# wchair.net
KiCad netlist of a schematic drawn in EAGLE
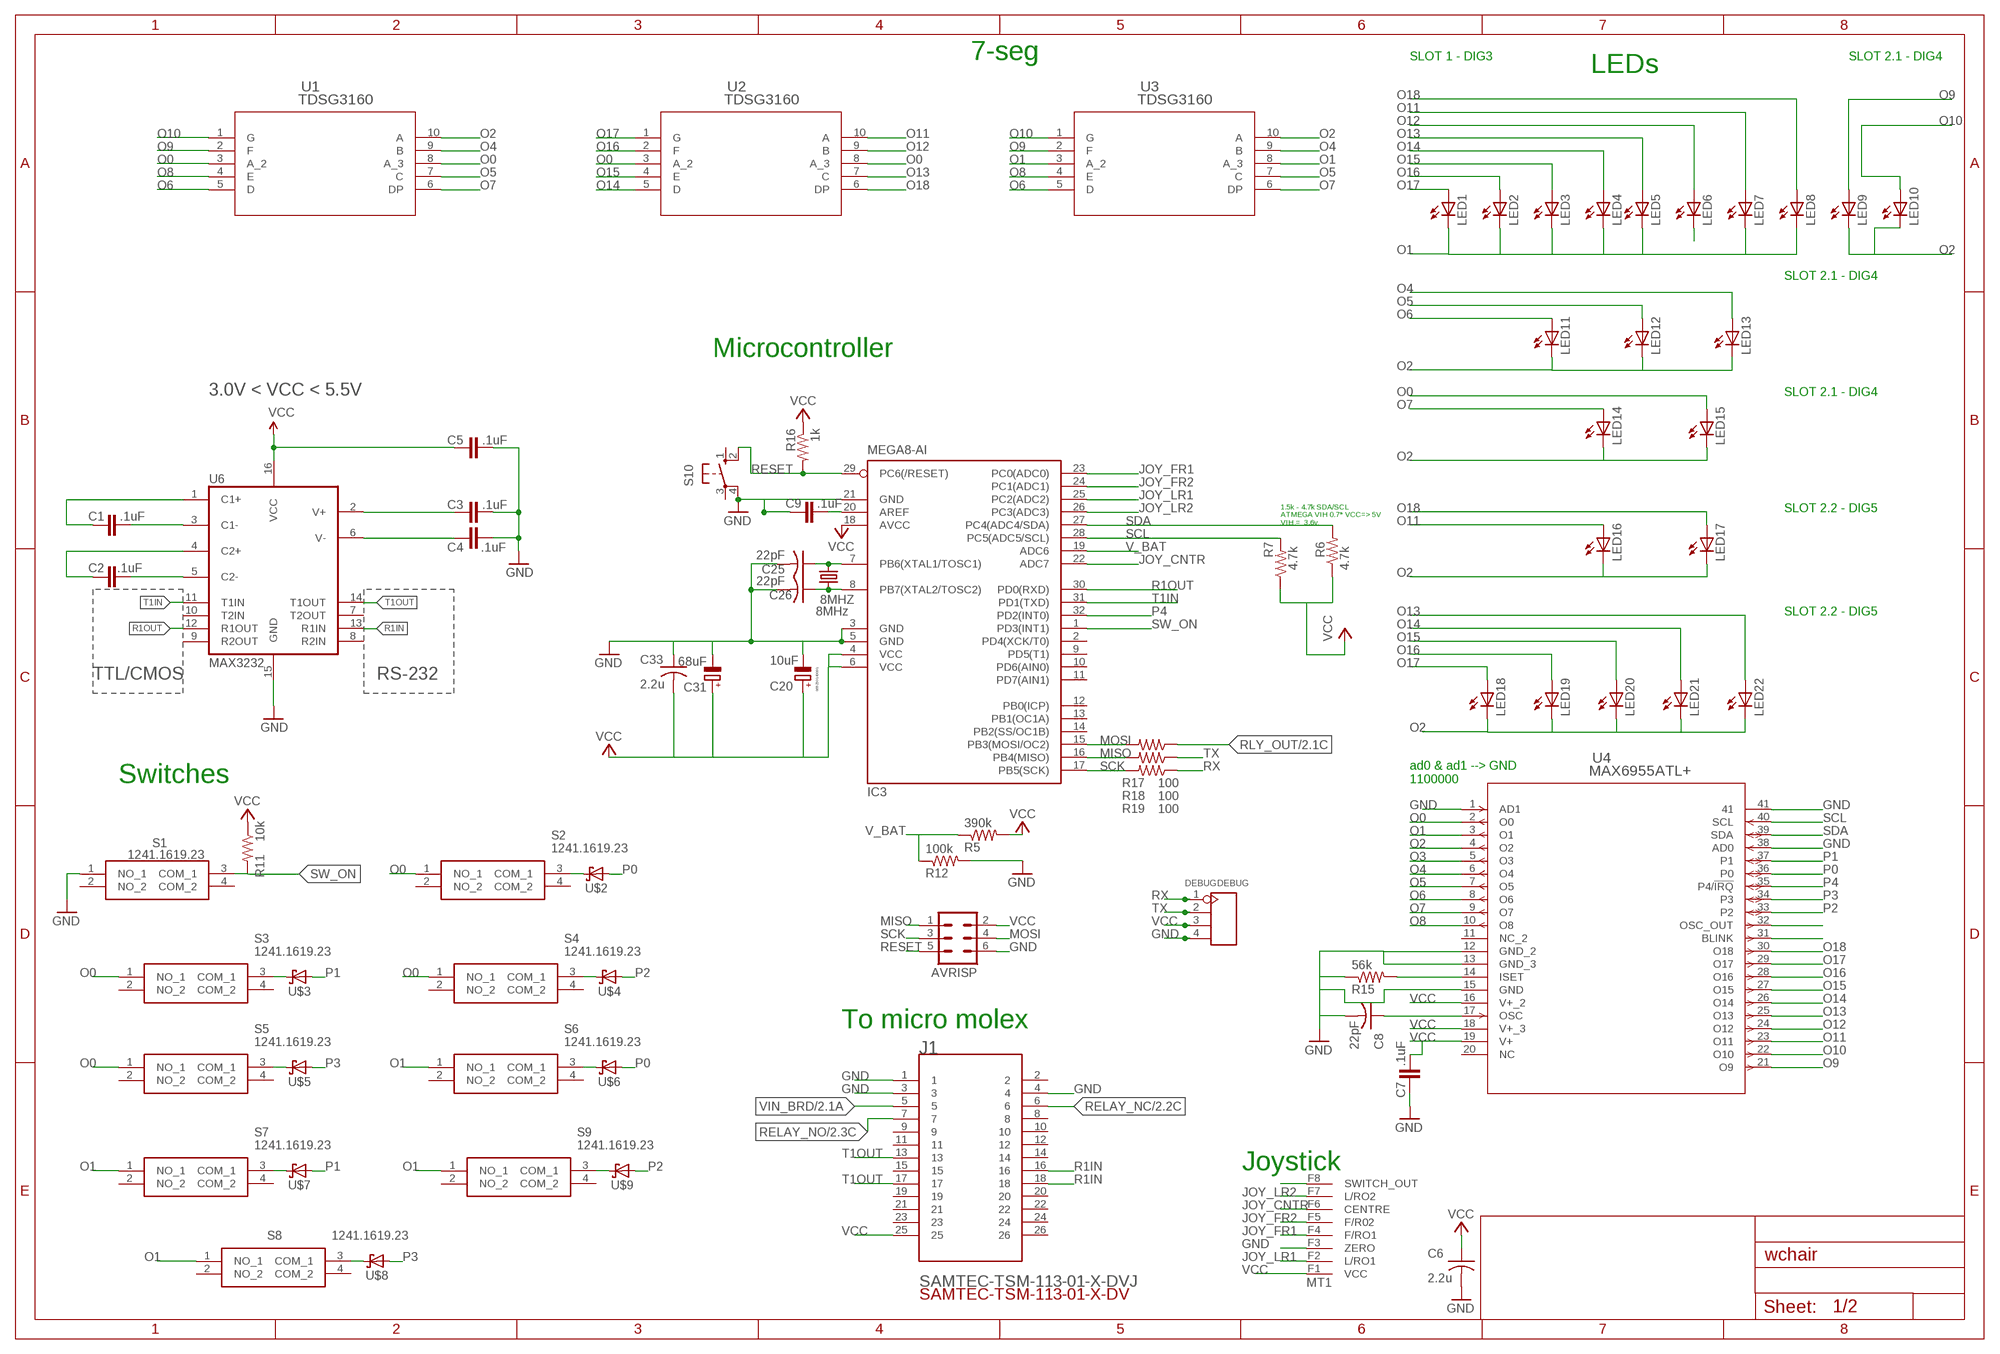
[diagram p0: schematic, sheet 1]
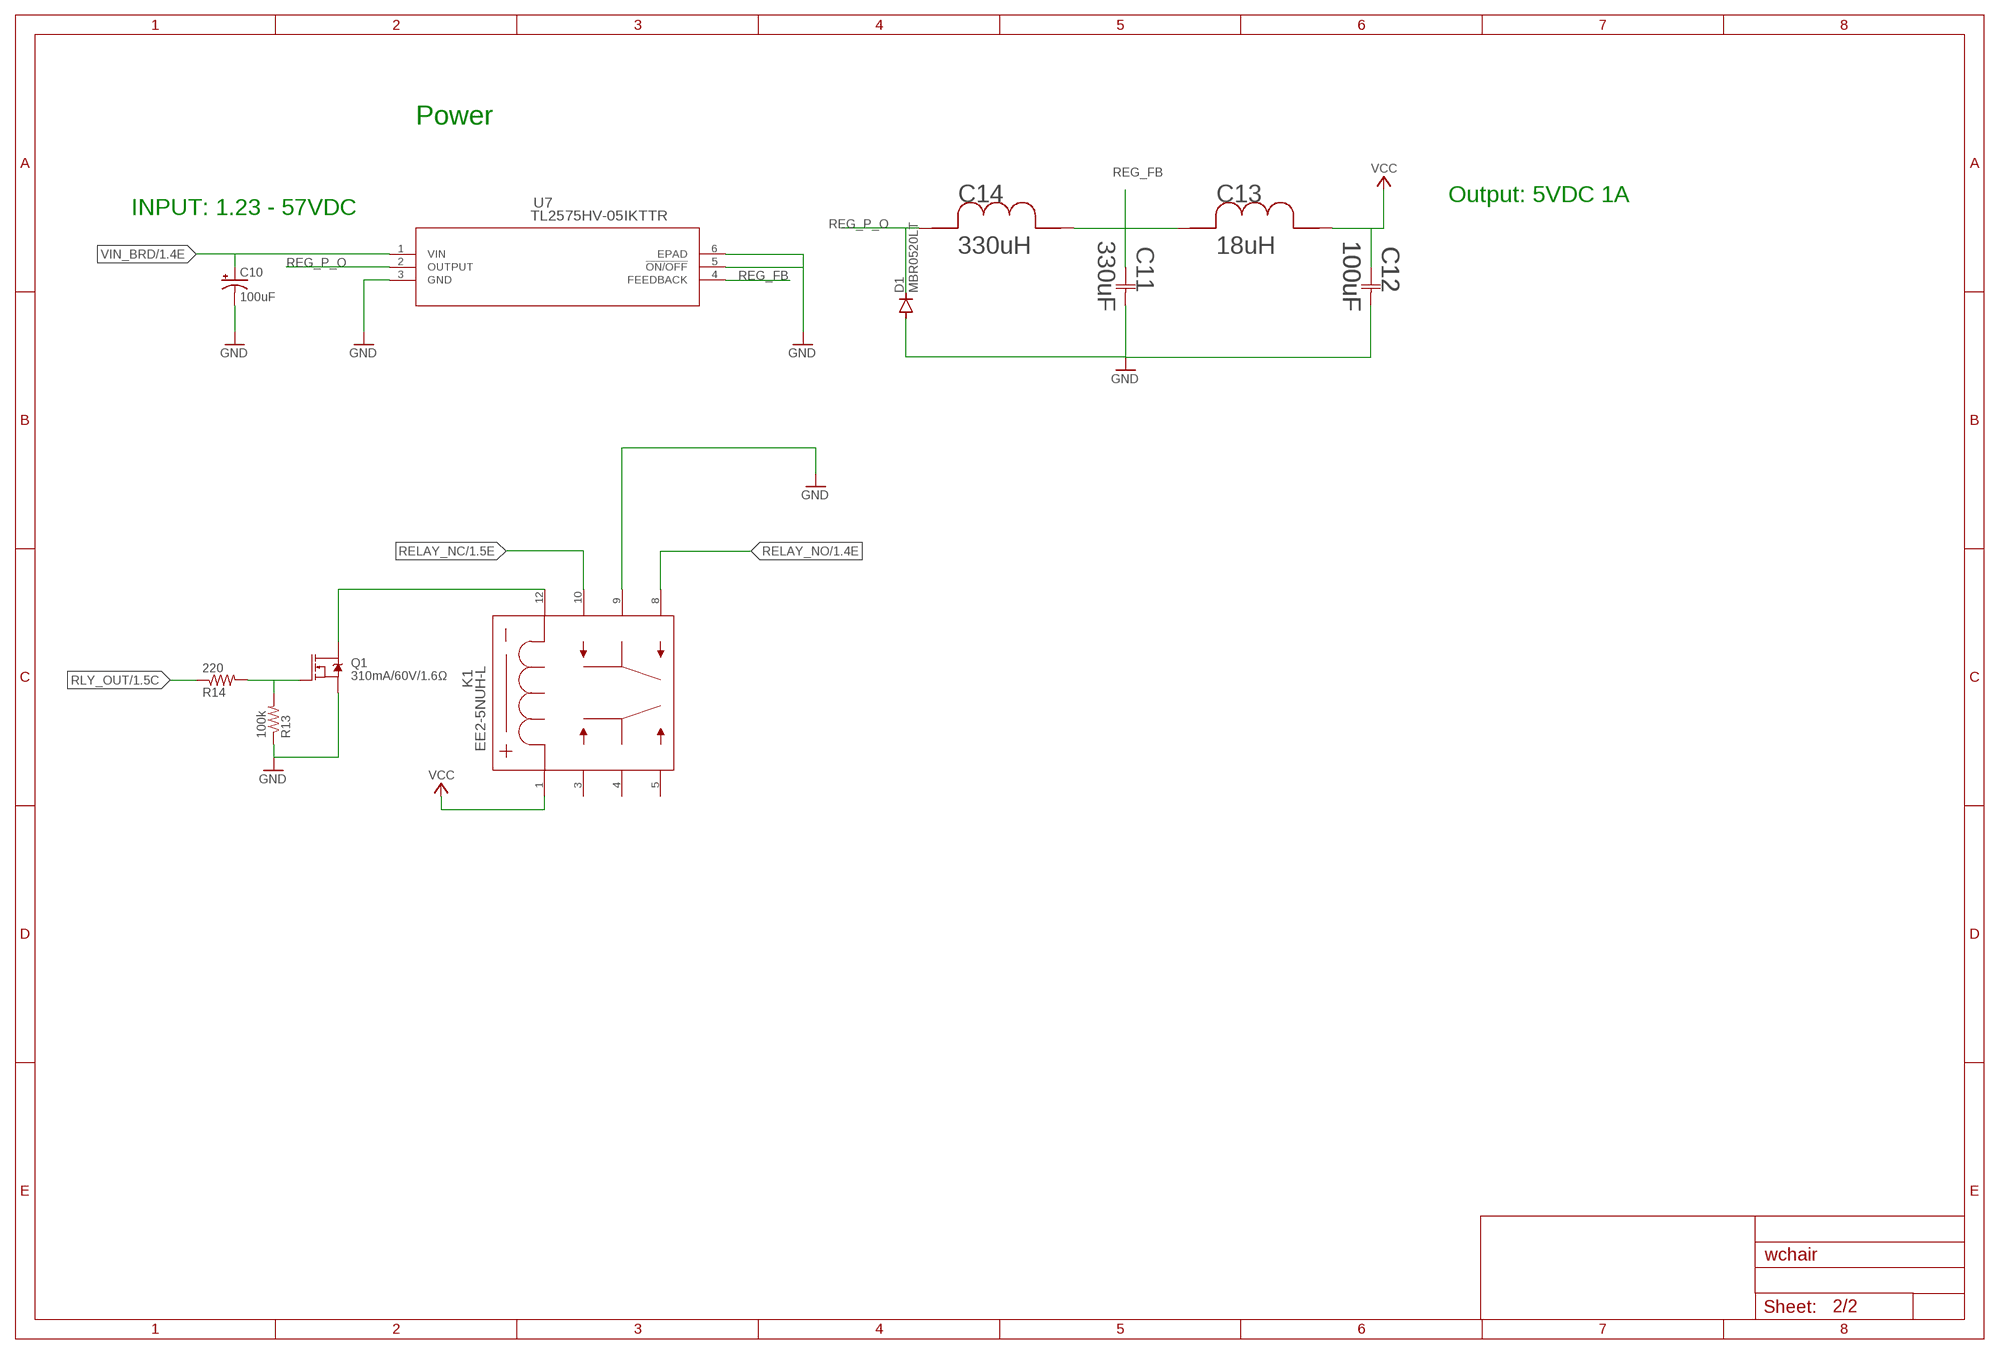
[diagram p1: schematic, sheet 2]

(export (version "E")
  (design (tool "Eeschema 10.0.6"))
  (components
    (comp (ref "C10")
      (value "100uF")
      (footprint "eagle-import:NIC_10X10.5_CAP")
      (fields (field (name "SPICEPREFIX") "C"))
      (libsource (lib "eagle-import") (part "100UF-POLAR-10X10.5-63V-20%"))
    )
    (comp (ref "C11")
      (value "330uF")
      (footprint "eagle-import:CAP_EEFK_D8")
      (fields (field (name "MANUFACTURER_PART_NUMBER") "EEEFK0J331XP"))
      (libsource (lib "eagle-import") (part "EEE-FK0J331XP"))
    )
    (comp (ref "C12")
      (value "100uF")
      (footprint "eagle-import:CAP_EEE_D")
      (fields (field (name "MANUFACTURER_PART_NUMBER") "EEE0JA101SP"))
      (libsource (lib "eagle-import") (part "EEE-0JA101SP"))
    )
    (comp (ref "C13")
      (value "18uH")
      (footprint "eagle-import:18UH2.15A")
      (libsource (lib "eagle-import") (part "INDUCTOR18UH2.15A"))
    )
    (comp (ref "C14")
      (value "330uH")
      (footprint "eagle-import:732-1698-1-ND")
      (libsource (lib "eagle-import") (part "INDUCTOR"))
    )
    (comp (ref "D1")
      (value "MBR0520LT")
      (footprint "eagle-import:SOD123")
      (libsource (lib "eagle-import") (part "MBR0520LT"))
    )
    (comp (ref "K1")
      (value "EE2-5NUH-L")
      (footprint "eagle-import:EE2NUH")
      (fields (field (name "MANUFACTURER_PART_NUMBER") "EE25NUHL"))
      (libsource (lib "eagle-import") (part "EE2-5NUH-L"))
    )
    (comp (ref "Q1")
      (value "310mA/60V/1.6Ω")
      (footprint "eagle-import:SOT323")
      (libsource (lib "eagle-import") (part "MOSFET-NCH-2N7002PW"))
    )
    (comp (ref "R13")
      (value "100k")
      (footprint "eagle-import:R0603")
      (libsource (lib "eagle-import") (part "R-US_R0603"))
    )
    (comp (ref "R14")
      (value "220")
      (footprint "eagle-import:R0603")
      (libsource (lib "eagle-import") (part "R-US_R0603"))
    )
    (comp (ref "U7")
      (value "TL2575HV-05IKTTR")
      (footprint "eagle-import:KTT5_6P22X6P86")
      (fields (field (name "MANUFACTURER_PART_NUMBER") "TL2575HV05IKTTR"))
      (libsource (lib "eagle-import") (part "TL2575HV-05IKTTR"))
    )
    (comp (ref "8MHZ")
      (value "8MHz")
      (footprint "eagle-import:SM49")
      (libsource (lib "eagle-import") (part "CRYSTALSM49"))
    )
    (comp (ref "AVRISP")
      (value "MA03-2")
      (footprint "eagle-import:MA03-2")
      (libsource (lib "eagle-import") (part "MA03-2"))
    )
    (comp (ref "C1")
      (value ".1uF")
      (footprint "eagle-import:0603-CAP")
      (fields (field (name "PROD_ID") "CAP-00810"))
      (libsource (lib "eagle-import") (part "0.1UF-25V(+80/-20%)(0603)"))
    )
    (comp (ref "C2")
      (value ".1uF")
      (footprint "eagle-import:0603-CAP")
      (fields (field (name "PROD_ID") "CAP-00810"))
      (libsource (lib "eagle-import") (part "0.1UF-25V(+80/-20%)(0603)"))
    )
    (comp (ref "C3")
      (value ".1uF")
      (footprint "eagle-import:0603-CAP")
      (fields (field (name "PROD_ID") "CAP-00810"))
      (libsource (lib "eagle-import") (part "0.1UF-25V(+80/-20%)(0603)"))
    )
    (comp (ref "C4")
      (value ".1uF")
      (footprint "eagle-import:0603-CAP")
      (fields (field (name "PROD_ID") "CAP-00810"))
      (libsource (lib "eagle-import") (part "0.1UF-25V(+80/-20%)(0603)"))
    )
    (comp (ref "C5")
      (value ".1uF")
      (footprint "eagle-import:0603-CAP")
      (fields (field (name "PROD_ID") "CAP-00810"))
      (libsource (lib "eagle-import") (part "0.1UF-25V(+80/-20%)(0603)"))
    )
    (comp (ref "C6")
      (value "2.2u")
      (footprint "eagle-import:C0603")
      (libsource (lib "eagle-import") (part "C-USC0603"))
    )
    (comp (ref "C7")
      (value ".1uF")
      (footprint "eagle-import:0603-CAP")
      (libsource (lib "eagle-import") (part "0.1UF-25V(+80/-20%)(0603)"))
    )
    (comp (ref "C8")
      (value "22pF")
      (footprint "eagle-import:C0603")
      (libsource (lib "eagle-import") (part "C-USC0603"))
    )
    (comp (ref "C9")
      (value ".1uF")
      (footprint "eagle-import:0603-CAP")
      (libsource (lib "eagle-import") (part "0.1UF-25V(+80/-20%)(0603)"))
    )
    (comp (ref "C20")
      (value "10uF")
      (footprint "eagle-import:153CLV-0405")
      (fields (field (name "CODE") "865250140001"))
      (libsource (lib "eagle-import") (part "CPOL-EU153CLV-0405"))
    )
    (comp (ref "C25")
      (value "22pF")
      (footprint "eagle-import:C0603")
      (libsource (lib "eagle-import") (part "C-USC0603"))
    )
    (comp (ref "C26")
      (value "22pF")
      (footprint "eagle-import:C0603")
      (libsource (lib "eagle-import") (part "C-USC0603"))
    )
    (comp (ref "C31")
      (value "68uF")
      (footprint "eagle-import:153CLV-0807")
      (libsource (lib "eagle-import") (part "CPOL-EU153CLV-0807"))
    )
    (comp (ref "C33")
      (value "2.2u")
      (footprint "eagle-import:C0603")
      (libsource (lib "eagle-import") (part "C-USC0603"))
    )
    (comp (ref "DEBUG")
      (value "DEBUG")
      (footprint "eagle-import:4-PIN-HEADER")
      (libsource (lib "eagle-import") (part "4-PIN-HEADER"))
    )
    (comp (ref "IC3")
      (value "MEGA8-AI")
      (footprint "eagle-import:TQFP32-08")
      (fields (field (name "MPN") "ATMEGA8-16AU"))
      (libsource (lib "eagle-import") (part "MEGA8-AI"))
    )
    (comp (ref "J1")
      (value "SAMTEC-TSM-113-01-X-DVJ")
      (footprint "eagle-import:SAMTEC-TSM-113-01-X-DV")
      (fields (field (name "MF") "Samtec Inc.") (field (name "MP") "TSM-113-01-L-DV"))
      (libsource (lib "eagle-import") (part "SAMTEC-TSM-113-01-X-DVJ"))
    )
    (comp (ref "LED1")
      (value "LEDCHIP-LED0805")
      (footprint "eagle-import:CHIP-LED0805")
      (libsource (lib "eagle-import") (part "LEDCHIP-LED0805"))
    )
    (comp (ref "LED2")
      (value "LEDCHIP-LED0805")
      (footprint "eagle-import:CHIP-LED0805")
      (libsource (lib "eagle-import") (part "LEDCHIP-LED0805"))
    )
    (comp (ref "LED3")
      (value "LEDCHIP-LED0805")
      (footprint "eagle-import:CHIP-LED0805")
      (libsource (lib "eagle-import") (part "LEDCHIP-LED0805"))
    )
    (comp (ref "LED4")
      (value "LEDCHIP-LED0805")
      (footprint "eagle-import:CHIP-LED0805")
      (libsource (lib "eagle-import") (part "LEDCHIP-LED0805"))
    )
    (comp (ref "LED5")
      (value "LEDCHIP-LED0805")
      (footprint "eagle-import:CHIP-LED0805")
      (libsource (lib "eagle-import") (part "LEDCHIP-LED0805"))
    )
    (comp (ref "LED6")
      (value "LEDCHIP-LED0805")
      (footprint "eagle-import:CHIP-LED0805")
      (libsource (lib "eagle-import") (part "LEDCHIP-LED0805"))
    )
    (comp (ref "LED7")
      (value "LEDCHIP-LED0805")
      (footprint "eagle-import:CHIP-LED0805")
      (libsource (lib "eagle-import") (part "LEDCHIP-LED0805"))
    )
    (comp (ref "LED8")
      (value "LEDCHIP-LED0805")
      (footprint "eagle-import:CHIP-LED0805")
      (libsource (lib "eagle-import") (part "LEDCHIP-LED0805"))
    )
    (comp (ref "LED9")
      (value "LEDCHIP-LED0805")
      (footprint "eagle-import:CHIP-LED0805")
      (libsource (lib "eagle-import") (part "LEDCHIP-LED0805"))
    )
    (comp (ref "LED10")
      (value "LEDCHIP-LED0805")
      (footprint "eagle-import:CHIP-LED0805")
      (libsource (lib "eagle-import") (part "LEDCHIP-LED0805"))
    )
    (comp (ref "LED11")
      (value "LEDCHIP-LED0805")
      (footprint "eagle-import:CHIP-LED0805")
      (libsource (lib "eagle-import") (part "LEDCHIP-LED0805"))
    )
    (comp (ref "LED12")
      (value "LEDCHIP-LED0805")
      (footprint "eagle-import:CHIP-LED0805")
      (libsource (lib "eagle-import") (part "LEDCHIP-LED0805"))
    )
    (comp (ref "LED13")
      (value "LEDCHIP-LED0805")
      (footprint "eagle-import:CHIP-LED0805")
      (libsource (lib "eagle-import") (part "LEDCHIP-LED0805"))
    )
    (comp (ref "LED14")
      (value "LEDCHIP-LED0805")
      (footprint "eagle-import:CHIP-LED0805")
      (libsource (lib "eagle-import") (part "LEDCHIP-LED0805"))
    )
    (comp (ref "LED15")
      (value "LEDCHIP-LED0805")
      (footprint "eagle-import:CHIP-LED0805")
      (libsource (lib "eagle-import") (part "LEDCHIP-LED0805"))
    )
    (comp (ref "LED16")
      (value "LEDCHIP-LED0805")
      (footprint "eagle-import:CHIP-LED0805")
      (libsource (lib "eagle-import") (part "LEDCHIP-LED0805"))
    )
    (comp (ref "LED17")
      (value "LEDCHIP-LED0805")
      (footprint "eagle-import:CHIP-LED0805")
      (libsource (lib "eagle-import") (part "LEDCHIP-LED0805"))
    )
    (comp (ref "LED18")
      (value "LEDCHIP-LED0805")
      (footprint "eagle-import:CHIP-LED0805")
      (libsource (lib "eagle-import") (part "LEDCHIP-LED0805"))
    )
    (comp (ref "LED19")
      (value "LEDCHIP-LED0805")
      (footprint "eagle-import:CHIP-LED0805")
      (libsource (lib "eagle-import") (part "LEDCHIP-LED0805"))
    )
    (comp (ref "LED20")
      (value "LEDCHIP-LED0805")
      (footprint "eagle-import:CHIP-LED0805")
      (libsource (lib "eagle-import") (part "LEDCHIP-LED0805"))
    )
    (comp (ref "LED21")
      (value "LEDCHIP-LED0805")
      (footprint "eagle-import:CHIP-LED0805")
      (libsource (lib "eagle-import") (part "LEDCHIP-LED0805"))
    )
    (comp (ref "LED22")
      (value "LEDCHIP-LED0805")
      (footprint "eagle-import:CHIP-LED0805")
      (libsource (lib "eagle-import") (part "LEDCHIP-LED0805"))
    )
    (comp (ref "MT1")
      (value "MINITEK2-8PINS")
      (footprint "eagle-import:MINITEK2-8PINS")
      (libsource (lib "eagle-import") (part "MINITEK2-8PINS"))
    )
    (comp (ref "R5")
      (value "390k")
      (footprint "eagle-import:R0603")
      (libsource (lib "eagle-import") (part "R-US_R0603"))
    )
    (comp (ref "R6")
      (value "4.7k")
      (footprint "eagle-import:R0603")
      (libsource (lib "eagle-import") (part "R-US_R0603"))
    )
    (comp (ref "R7")
      (value "4.7k")
      (footprint "eagle-import:R0603")
      (libsource (lib "eagle-import") (part "R-US_R0603"))
    )
    (comp (ref "R11")
      (value "10k")
      (footprint "eagle-import:R0603")
      (libsource (lib "eagle-import") (part "rcl_R-US_R0603"))
    )
    (comp (ref "R12")
      (value "100k")
      (footprint "eagle-import:R0603")
      (libsource (lib "eagle-import") (part "R-US_R0603"))
    )
    (comp (ref "R15")
      (value "56k")
      (footprint "eagle-import:R0603")
      (libsource (lib "eagle-import") (part "R-US_R0603"))
    )
    (comp (ref "R16")
      (value "1k")
      (footprint "eagle-import:R0603")
      (libsource (lib "eagle-import") (part "rcl_R-US_R0603"))
    )
    (comp (ref "R17")
      (value "100")
      (footprint "eagle-import:R0603")
      (libsource (lib "eagle-import") (part "rcl_R-US_R0603"))
    )
    (comp (ref "R18")
      (value "100")
      (footprint "eagle-import:R0603")
      (libsource (lib "eagle-import") (part "rcl_R-US_R0603"))
    )
    (comp (ref "R19")
      (value "100")
      (footprint "eagle-import:R0603")
      (libsource (lib "eagle-import") (part "rcl_R-US_R0603"))
    )
    (comp (ref "S1")
      (value "1241.1619.23")
      (footprint "eagle-import:IP40-J-LEAD")
      (fields (field (name "MOUSER_PART_NUMBER") "693-1241.1619.23"))
      (libsource (lib "eagle-import") (part "1241.1619.23"))
    )
    (comp (ref "S2")
      (value "1241.1619.23")
      (footprint "eagle-import:IP40-J-LEAD")
      (fields (field (name "MOUSER_PART_NUMBER") "693-1241.1619.23"))
      (libsource (lib "eagle-import") (part "1241.1619.23"))
    )
    (comp (ref "S3")
      (value "1241.1619.23")
      (footprint "eagle-import:IP40-J-LEAD")
      (fields (field (name "MOUSER_PART_NUMBER") "693-1241.1619.23"))
      (libsource (lib "eagle-import") (part "1241.1619.23"))
    )
    (comp (ref "S4")
      (value "1241.1619.23")
      (footprint "eagle-import:IP40-J-LEAD")
      (fields (field (name "MOUSER_PART_NUMBER") "693-1241.1619.23"))
      (libsource (lib "eagle-import") (part "1241.1619.23"))
    )
    (comp (ref "S5")
      (value "1241.1619.23")
      (footprint "eagle-import:IP40-J-LEAD")
      (fields (field (name "MOUSER_PART_NUMBER") "693-1241.1619.23"))
      (libsource (lib "eagle-import") (part "1241.1619.23"))
    )
    (comp (ref "S6")
      (value "1241.1619.23")
      (footprint "eagle-import:IP40-J-LEAD")
      (fields (field (name "MOUSER_PART_NUMBER") "693-1241.1619.23"))
      (libsource (lib "eagle-import") (part "1241.1619.23"))
    )
    (comp (ref "S7")
      (value "1241.1619.23")
      (footprint "eagle-import:IP40-J-LEAD")
      (fields (field (name "MOUSER_PART_NUMBER") "693-1241.1619.23"))
      (libsource (lib "eagle-import") (part "1241.1619.23"))
    )
    (comp (ref "S8")
      (value "1241.1619.23")
      (footprint "eagle-import:IP40-J-LEAD")
      (fields (field (name "MOUSER_PART_NUMBER") "693-1241.1619.23"))
      (libsource (lib "eagle-import") (part "1241.1619.23"))
    )
    (comp (ref "S9")
      (value "1241.1619.23")
      (footprint "eagle-import:IP40-J-LEAD")
      (fields (field (name "MOUSER_PART_NUMBER") "693-1241.1619.23"))
      (libsource (lib "eagle-import") (part "1241.1619.23"))
    )
    (comp (ref "S10")
      (value "10-XX")
      (footprint "eagle-import:B3F-10XX")
      (fields (field (name "MPN") "B3F-1000"))
      (libsource (lib "eagle-import") (part "10-XX"))
    )
    (comp (ref "U$2")
      (value "SCHOTTKY")
      (footprint "eagle-import:SOD-323")
      (libsource (lib "eagle-import") (part "SCHOTTKY"))
    )
    (comp (ref "U$3")
      (value "SCHOTTKY")
      (footprint "eagle-import:SOD-323")
      (libsource (lib "eagle-import") (part "SCHOTTKY"))
    )
    (comp (ref "U$4")
      (value "SCHOTTKY")
      (footprint "eagle-import:SOD-323")
      (libsource (lib "eagle-import") (part "SCHOTTKY"))
    )
    (comp (ref "U$5")
      (value "SCHOTTKY")
      (footprint "eagle-import:SOD-323")
      (libsource (lib "eagle-import") (part "SCHOTTKY"))
    )
    (comp (ref "U$6")
      (value "SCHOTTKY")
      (footprint "eagle-import:SOD-323")
      (libsource (lib "eagle-import") (part "SCHOTTKY"))
    )
    (comp (ref "U$7")
      (value "SCHOTTKY")
      (footprint "eagle-import:SOD-323")
      (libsource (lib "eagle-import") (part "SCHOTTKY"))
    )
    (comp (ref "U$8")
      (value "SCHOTTKY")
      (footprint "eagle-import:SOD-323")
      (libsource (lib "eagle-import") (part "SCHOTTKY"))
    )
    (comp (ref "U$9")
      (value "SCHOTTKY")
      (footprint "eagle-import:SOD-323")
      (libsource (lib "eagle-import") (part "SCHOTTKY"))
    )
    (comp (ref "U1")
      (value "TDSG3160")
      (footprint "eagle-import:DIP10_TDS")
      (libsource (lib "eagle-import") (part "TDSG3160"))
    )
    (comp (ref "U2")
      (value "TDSG3160")
      (footprint "eagle-import:DIP10_TDS")
      (libsource (lib "eagle-import") (part "TDSG3160"))
    )
    (comp (ref "U3")
      (value "TDSG3160")
      (footprint "eagle-import:DIP10_TDS")
      (libsource (lib "eagle-import") (part "TDSG3160"))
    )
    (comp (ref "U4")
      (value "MAX6955ATL+")
      (footprint "eagle-import:21-0141I_T4066-5")
      (libsource (lib "eagle-import") (part "MAX6955ATL+"))
    )
    (comp (ref "U6")
      (value "MAX3232")
      (footprint "eagle-import:SO16")
      (libsource (lib "eagle-import") (part "MAX2323SOIC16"))
    )
  )
  (nets
    (net (code "1") (name "GND") (class "Default")
      (node (ref "AVRISP") (pin "6") (pinfunction "6_6") (pintype "passive"))
      (node (ref "C10") (pin "-") (pinfunction "-_-") (pintype "passive"))
      (node (ref "C11") (pin "2") (pinfunction "2_2") (pintype "passive"))
      (node (ref "C12") (pin "2") (pinfunction "2_2") (pintype "passive"))
      (node (ref "C20") (pin "-") (pinfunction "-_-") (pintype "passive"))
      (node (ref "C25") (pin "2") (pinfunction "2_2") (pintype "passive"))
      (node (ref "C26") (pin "2") (pinfunction "2_2") (pintype "passive"))
      (node (ref "C3") (pin "2") (pinfunction "2_2") (pintype "passive"))
      (node (ref "C31") (pin "-") (pinfunction "-_-") (pintype "passive"))
      (node (ref "C33") (pin "1") (pinfunction "1_1") (pintype "passive"))
      (node (ref "C4") (pin "2") (pinfunction "2_2") (pintype "passive"))
      (node (ref "C5") (pin "2") (pinfunction "2_2") (pintype "passive"))
      (node (ref "C6") (pin "2") (pinfunction "2_2") (pintype "passive"))
      (node (ref "C7") (pin "1") (pinfunction "1_1") (pintype "passive"))
      (node (ref "C8") (pin "2") (pinfunction "2_2") (pintype "passive"))
      (node (ref "C9") (pin "1") (pinfunction "1_1") (pintype "passive"))
      (node (ref "D1") (pin "A") (pinfunction "A_A") (pintype "passive"))
      (node (ref "DEBUG") (pin "4") (pinfunction "P$4_4") (pintype "bidirectional"))
      (node (ref "IC3") (pin "21") (pinfunction "GND_21") (pintype "power_in"))
      (node (ref "IC3") (pin "3") (pinfunction "GND_3") (pintype "power_in"))
      (node (ref "IC3") (pin "5") (pinfunction "GND_5") (pintype "power_in"))
      (node (ref "J1") (pin "1") (pinfunction "1_1") (pintype "passive"))
      (node (ref "J1") (pin "3") (pinfunction "3_3") (pintype "passive"))
      (node (ref "J1") (pin "4") (pinfunction "4_4") (pintype "passive"))
      (node (ref "K1") (pin "9") (pinfunction "6_9") (pintype "passive"))
      (node (ref "MT1") (pin "F3") (pinfunction "ZERO_F3") (pintype "bidirectional"))
      (node (ref "Q1") (pin "2") (pinfunction "S_2") (pintype "bidirectional"))
      (node (ref "R12") (pin "2") (pinfunction "2_2") (pintype "passive"))
      (node (ref "R13") (pin "1") (pinfunction "1_1") (pintype "passive"))
      (node (ref "R15") (pin "1") (pinfunction "1_1") (pintype "passive"))
      (node (ref "S1") (pin "1") (pinfunction "NO_1_1") (pintype "bidirectional"))
      (node (ref "S10") (pin "4") (pinfunction "P1_4") (pintype "passive"))
      (node (ref "U4") (pin "1") (pinfunction "AD1_1") (pintype "input"))
      (node (ref "U4") (pin "12") (pinfunction "GND_2_12") (pintype "power_in"))
      (node (ref "U4") (pin "13") (pinfunction "GND_3_13") (pintype "power_in"))
      (node (ref "U4") (pin "15") (pinfunction "GND_15") (pintype "power_in"))
      (node (ref "U4") (pin "38") (pinfunction "AD0_38") (pintype "input"))
      (node (ref "U4") (pin "41") (pinfunction "41_41") (pintype "passive"))
      (node (ref "U6") (pin "15") (pinfunction "GND_15") (pintype "bidirectional"))
      (node (ref "U7") (pin "3") (pinfunction "GND_3") (pintype "power_in"))
      (node (ref "U7") (pin "5") (pinfunction "~{ON/OFF}_5") (pintype "passive"))
      (node (ref "U7") (pin "6") (pinfunction "EPAD_6") (pintype "passive"))
    )
    (net (code "2") (name "JOY_CNTR") (class "Default")
      (node (ref "IC3") (pin "22") (pinfunction "ADC7_22") (pintype "bidirectional"))
      (node (ref "MT1") (pin "F6") (pinfunction "CENTRE_F6") (pintype "bidirectional"))
    )
    (net (code "3") (name "JOY_FR1") (class "Default")
      (node (ref "IC3") (pin "23") (pinfunction "PC0(ADC0)_23") (pintype "bidirectional"))
      (node (ref "MT1") (pin "F4") (pinfunction "F/RO1_F4") (pintype "bidirectional"))
    )
    (net (code "4") (name "JOY_FR2") (class "Default")
      (node (ref "IC3") (pin "24") (pinfunction "PC1(ADC1)_24") (pintype "bidirectional"))
      (node (ref "MT1") (pin "F5") (pinfunction "F/R02_F5") (pintype "bidirectional"))
    )
    (net (code "5") (name "JOY_LR1") (class "Default")
      (node (ref "IC3") (pin "25") (pinfunction "PC2(ADC2)_25") (pintype "bidirectional"))
      (node (ref "MT1") (pin "F2") (pinfunction "L/RO1_F2") (pintype "bidirectional"))
    )
    (net (code "6") (name "JOY_LR2") (class "Default")
      (node (ref "IC3") (pin "26") (pinfunction "PC3(ADC3)_26") (pintype "bidirectional"))
      (node (ref "MT1") (pin "F7") (pinfunction "L/RO2_F7") (pintype "bidirectional"))
    )
    (net (code "7") (name "MISO") (class "Default")
      (node (ref "AVRISP") (pin "1") (pinfunction "1_1") (pintype "passive"))
      (node (ref "IC3") (pin "16") (pinfunction "PB4(MISO)_16") (pintype "bidirectional"))
      (node (ref "R18") (pin "2") (pinfunction "2_2") (pintype "passive"))
    )
    (net (code "8") (name "MOSI") (class "Default")
      (node (ref "AVRISP") (pin "4") (pinfunction "4_4") (pintype "passive"))
      (node (ref "IC3") (pin "15") (pinfunction "PB3(MOSI/OC2)_15") (pintype "bidirectional"))
      (node (ref "R19") (pin "2") (pinfunction "2_2") (pintype "passive"))
    )
    (net (code "9") (name "Net-(IC3-AREF)") (class "Default")
      (node (ref "C9") (pin "2") (pinfunction "2_2") (pintype "passive"))
      (node (ref "IC3") (pin "20") (pinfunction "AREF_20") (pintype "passive"))
    )
    (net (code "10") (name "Net-(IC3-PB6(XTAL1{slash}TOSC1))") (class "Default")
      (node (ref "8MHZ") (pin "2") (pinfunction "2_2") (pintype "passive"))
      (node (ref "C25") (pin "1") (pinfunction "1_1") (pintype "passive"))
      (node (ref "IC3") (pin "7") (pinfunction "PB6(XTAL1/TOSC1)_7") (pintype "bidirectional"))
    )
    (net (code "11") (name "Net-(IC3-PB7(XTAL2{slash}TOSC2))") (class "Default")
      (node (ref "8MHZ") (pin "1") (pinfunction "1_1") (pintype "passive"))
      (node (ref "C26") (pin "1") (pinfunction "1_1") (pintype "passive"))
      (node (ref "IC3") (pin "8") (pinfunction "PB7(XTAL2/TOSC2)_8") (pintype "bidirectional"))
    )
    (net (code "12") (name "Net-(K1-8)") (class "Default")
      (node (ref "K1") (pin "12") (pinfunction "8_12") (pintype "passive"))
      (node (ref "Q1") (pin "3") (pinfunction "D_3") (pintype "bidirectional"))
    )
    (net (code "13") (name "Net-(Q1-G)") (class "Default")
      (node (ref "Q1") (pin "1") (pinfunction "G_1") (pintype "bidirectional"))
      (node (ref "R13") (pin "2") (pinfunction "2_2") (pintype "passive"))
      (node (ref "R14") (pin "2") (pinfunction "2_2") (pintype "passive"))
    )
    (net (code "14") (name "Net-(S2-COM_1)") (class "Default")
      (node (ref "S2") (pin "3") (pinfunction "COM_1_3") (pintype "bidirectional"))
      (node (ref "U$2") (pin "C") (pinfunction "C_C") (pintype "passive"))
    )
    (net (code "15") (name "Net-(S3-COM_1)") (class "Default")
      (node (ref "S3") (pin "3") (pinfunction "COM_1_3") (pintype "bidirectional"))
      (node (ref "U$3") (pin "C") (pinfunction "C_C") (pintype "passive"))
    )
    (net (code "16") (name "Net-(S4-COM_1)") (class "Default")
      (node (ref "S4") (pin "3") (pinfunction "COM_1_3") (pintype "bidirectional"))
      (node (ref "U$4") (pin "C") (pinfunction "C_C") (pintype "passive"))
    )
    (net (code "17") (name "Net-(S5-COM_1)") (class "Default")
      (node (ref "S5") (pin "3") (pinfunction "COM_1_3") (pintype "bidirectional"))
      (node (ref "U$5") (pin "C") (pinfunction "C_C") (pintype "passive"))
    )
    (net (code "18") (name "Net-(S6-COM_1)") (class "Default")
      (node (ref "S6") (pin "3") (pinfunction "COM_1_3") (pintype "bidirectional"))
      (node (ref "U$6") (pin "C") (pinfunction "C_C") (pintype "passive"))
    )
    (net (code "19") (name "Net-(S7-COM_1)") (class "Default")
      (node (ref "S7") (pin "3") (pinfunction "COM_1_3") (pintype "bidirectional"))
      (node (ref "U$7") (pin "C") (pinfunction "C_C") (pintype "passive"))
    )
    (net (code "20") (name "Net-(S8-COM_1)") (class "Default")
      (node (ref "S8") (pin "3") (pinfunction "COM_1_3") (pintype "bidirectional"))
      (node (ref "U$8") (pin "C") (pinfunction "C_C") (pintype "passive"))
    )
    (net (code "21") (name "Net-(S9-COM_1)") (class "Default")
      (node (ref "S9") (pin "3") (pinfunction "COM_1_3") (pintype "bidirectional"))
      (node (ref "U$9") (pin "C") (pinfunction "C_C") (pintype "passive"))
    )
    (net (code "22") (name "Net-(U4-ISET)") (class "Default")
      (node (ref "R15") (pin "2") (pinfunction "2_2") (pintype "passive"))
      (node (ref "U4") (pin "14") (pinfunction "ISET_14") (pintype "passive"))
    )
    (net (code "23") (name "Net-(U4-OSC)") (class "Default")
      (node (ref "C8") (pin "1") (pinfunction "1_1") (pintype "passive"))
      (node (ref "U4") (pin "17") (pinfunction "OSC_17") (pintype "input"))
    )
    (net (code "24") (name "Net-(U6-C1+)") (class "Default")
      (node (ref "C1") (pin "1") (pinfunction "1_1") (pintype "passive"))
      (node (ref "U6") (pin "1") (pinfunction "C1+_1") (pintype "bidirectional"))
    )
    (net (code "25") (name "Net-(U6-C1-)") (class "Default")
      (node (ref "C1") (pin "2") (pinfunction "2_2") (pintype "passive"))
      (node (ref "U6") (pin "3") (pinfunction "C1-_3") (pintype "bidirectional"))
    )
    (net (code "26") (name "Net-(U6-C2+)") (class "Default")
      (node (ref "C2") (pin "1") (pinfunction "1_1") (pintype "passive"))
      (node (ref "U6") (pin "4") (pinfunction "C2+_4") (pintype "bidirectional"))
    )
    (net (code "27") (name "Net-(U6-C2-)") (class "Default")
      (node (ref "C2") (pin "2") (pinfunction "2_2") (pintype "passive"))
      (node (ref "U6") (pin "5") (pinfunction "C2-_5") (pintype "bidirectional"))
    )
    (net (code "28") (name "Net-(U6-V+)") (class "Default")
      (node (ref "C3") (pin "1") (pinfunction "1_1") (pintype "passive"))
      (node (ref "U6") (pin "2") (pinfunction "V+_2") (pintype "bidirectional"))
    )
    (net (code "29") (name "Net-(U6-V-)") (class "Default")
      (node (ref "C4") (pin "1") (pinfunction "1_1") (pintype "passive"))
      (node (ref "U6") (pin "6") (pinfunction "V-_6") (pintype "bidirectional"))
    )
    (net (code "30") (name "O0") (class "Default")
      (node (ref "LED15") (pin "A") (pinfunction "A_A") (pintype "passive"))
      (node (ref "S2") (pin "1") (pinfunction "NO_1_1") (pintype "bidirectional"))
      (node (ref "S3") (pin "1") (pinfunction "NO_1_1") (pintype "bidirectional"))
      (node (ref "S4") (pin "1") (pinfunction "NO_1_1") (pintype "bidirectional"))
      (node (ref "S5") (pin "1") (pinfunction "NO_1_1") (pintype "bidirectional"))
      (node (ref "U1") (pin "3") (pinfunction "A_2_3") (pintype "passive"))
      (node (ref "U1") (pin "8") (pinfunction "A_3_8") (pintype "passive"))
      (node (ref "U2") (pin "3") (pinfunction "A_2_3") (pintype "passive"))
      (node (ref "U2") (pin "8") (pinfunction "A_3_8") (pintype "passive"))
      (node (ref "U4") (pin "2") (pinfunction "O0_2") (pintype "output"))
    )
    (net (code "31") (name "O1") (class "Default")
      (node (ref "LED1") (pin "C") (pinfunction "C_C") (pintype "passive"))
      (node (ref "LED2") (pin "C") (pinfunction "C_C") (pintype "passive"))
      (node (ref "LED3") (pin "C") (pinfunction "C_C") (pintype "passive"))
      (node (ref "LED4") (pin "C") (pinfunction "C_C") (pintype "passive"))
      (node (ref "LED5") (pin "C") (pinfunction "C_C") (pintype "passive"))
      (node (ref "LED7") (pin "C") (pinfunction "C_C") (pintype "passive"))
      (node (ref "LED8") (pin "C") (pinfunction "C_C") (pintype "passive"))
      (node (ref "S6") (pin "1") (pinfunction "NO_1_1") (pintype "bidirectional"))
      (node (ref "S7") (pin "1") (pinfunction "NO_1_1") (pintype "bidirectional"))
      (node (ref "S8") (pin "1") (pinfunction "NO_1_1") (pintype "bidirectional"))
      (node (ref "S9") (pin "1") (pinfunction "NO_1_1") (pintype "bidirectional"))
      (node (ref "U3") (pin "3") (pinfunction "A_2_3") (pintype "passive"))
      (node (ref "U3") (pin "8") (pinfunction "A_3_8") (pintype "passive"))
      (node (ref "U4") (pin "3") (pinfunction "O1_3") (pintype "output"))
    )
    (net (code "32") (name "O2") (class "Default")
      (node (ref "LED10") (pin "C") (pinfunction "C_C") (pintype "passive"))
      (node (ref "LED11") (pin "C") (pinfunction "C_C") (pintype "passive"))
      (node (ref "LED12") (pin "C") (pinfunction "C_C") (pintype "passive"))
      (node (ref "LED13") (pin "C") (pinfunction "C_C") (pintype "passive"))
      (node (ref "LED14") (pin "C") (pinfunction "C_C") (pintype "passive"))
      (node (ref "LED15") (pin "C") (pinfunction "C_C") (pintype "passive"))
      (node (ref "LED16") (pin "C") (pinfunction "C_C") (pintype "passive"))
      (node (ref "LED17") (pin "C") (pinfunction "C_C") (pintype "passive"))
      (node (ref "LED18") (pin "C") (pinfunction "C_C") (pintype "passive"))
      (node (ref "LED19") (pin "C") (pinfunction "C_C") (pintype "passive"))
      (node (ref "LED20") (pin "C") (pinfunction "C_C") (pintype "passive"))
      (node (ref "LED21") (pin "C") (pinfunction "C_C") (pintype "passive"))
      (node (ref "LED22") (pin "C") (pinfunction "C_C") (pintype "passive"))
      (node (ref "LED9") (pin "C") (pinfunction "C_C") (pintype "passive"))
      (node (ref "U1") (pin "10") (pinfunction "A_10") (pintype "passive"))
      (node (ref "U3") (pin "10") (pinfunction "A_10") (pintype "passive"))
      (node (ref "U4") (pin "4") (pinfunction "O2_4") (pintype "output"))
    )
    (net (code "33") (name "O3") (class "Default")
      (node (ref "U4") (pin "5") (pinfunction "O3_5") (pintype "output"))
    )
    (net (code "34") (name "O4") (class "Default")
      (node (ref "LED13") (pin "A") (pinfunction "A_A") (pintype "passive"))
      (node (ref "U1") (pin "9") (pinfunction "B_9") (pintype "passive"))
      (node (ref "U3") (pin "9") (pinfunction "B_9") (pintype "passive"))
      (node (ref "U4") (pin "6") (pinfunction "O4_6") (pintype "output"))
    )
    (net (code "35") (name "O5") (class "Default")
      (node (ref "LED12") (pin "A") (pinfunction "A_A") (pintype "passive"))
      (node (ref "U1") (pin "7") (pinfunction "C_7") (pintype "passive"))
      (node (ref "U3") (pin "7") (pinfunction "C_7") (pintype "passive"))
      (node (ref "U4") (pin "7") (pinfunction "O5_7") (pintype "output"))
    )
    (net (code "36") (name "O6") (class "Default")
      (node (ref "LED11") (pin "A") (pinfunction "A_A") (pintype "passive"))
      (node (ref "U1") (pin "5") (pinfunction "D_5") (pintype "passive"))
      (node (ref "U3") (pin "5") (pinfunction "D_5") (pintype "passive"))
      (node (ref "U4") (pin "8") (pinfunction "O6_8") (pintype "output"))
    )
    (net (code "37") (name "O7") (class "Default")
      (node (ref "LED14") (pin "A") (pinfunction "A_A") (pintype "passive"))
      (node (ref "U1") (pin "6") (pinfunction "DP_6") (pintype "passive"))
      (node (ref "U3") (pin "6") (pinfunction "DP_6") (pintype "passive"))
      (node (ref "U4") (pin "9") (pinfunction "O7_9") (pintype "output"))
    )
    (net (code "38") (name "O8") (class "Default")
      (node (ref "U1") (pin "4") (pinfunction "E_4") (pintype "passive"))
      (node (ref "U3") (pin "4") (pinfunction "E_4") (pintype "passive"))
      (node (ref "U4") (pin "10") (pinfunction "O8_10") (pintype "output"))
    )
    (net (code "39") (name "O9") (class "Default")
      (node (ref "LED9") (pin "A") (pinfunction "A_A") (pintype "passive"))
      (node (ref "U1") (pin "2") (pinfunction "F_2") (pintype "passive"))
      (node (ref "U3") (pin "2") (pinfunction "F_2") (pintype "passive"))
      (node (ref "U4") (pin "21") (pinfunction "O9_21") (pintype "output"))
    )
    (net (code "40") (name "O10") (class "Default")
      (node (ref "LED10") (pin "A") (pinfunction "A_A") (pintype "passive"))
      (node (ref "U1") (pin "1") (pinfunction "G_1") (pintype "passive"))
      (node (ref "U3") (pin "1") (pinfunction "G_1") (pintype "passive"))
      (node (ref "U4") (pin "22") (pinfunction "O10_22") (pintype "output"))
    )
    (net (code "41") (name "O11") (class "Default")
      (node (ref "LED16") (pin "A") (pinfunction "A_A") (pintype "passive"))
      (node (ref "LED7") (pin "A") (pinfunction "A_A") (pintype "passive"))
      (node (ref "U2") (pin "10") (pinfunction "A_10") (pintype "passive"))
      (node (ref "U4") (pin "23") (pinfunction "O11_23") (pintype "output"))
    )
    (net (code "42") (name "O12") (class "Default")
      (node (ref "LED6") (pin "A") (pinfunction "A_A") (pintype "passive"))
      (node (ref "U2") (pin "9") (pinfunction "B_9") (pintype "passive"))
      (node (ref "U4") (pin "24") (pinfunction "O12_24") (pintype "output"))
    )
    (net (code "43") (name "O13") (class "Default")
      (node (ref "LED22") (pin "A") (pinfunction "A_A") (pintype "passive"))
      (node (ref "LED5") (pin "A") (pinfunction "A_A") (pintype "passive"))
      (node (ref "U2") (pin "7") (pinfunction "C_7") (pintype "passive"))
      (node (ref "U4") (pin "25") (pinfunction "O13_25") (pintype "output"))
    )
    (net (code "44") (name "O14") (class "Default")
      (node (ref "LED21") (pin "A") (pinfunction "A_A") (pintype "passive"))
      (node (ref "LED4") (pin "A") (pinfunction "A_A") (pintype "passive"))
      (node (ref "U2") (pin "5") (pinfunction "D_5") (pintype "passive"))
      (node (ref "U4") (pin "26") (pinfunction "O14_26") (pintype "output"))
    )
    (net (code "45") (name "O15") (class "Default")
      (node (ref "LED20") (pin "A") (pinfunction "A_A") (pintype "passive"))
      (node (ref "LED3") (pin "A") (pinfunction "A_A") (pintype "passive"))
      (node (ref "U2") (pin "4") (pinfunction "E_4") (pintype "passive"))
      (node (ref "U4") (pin "27") (pinfunction "O15_27") (pintype "output"))
    )
    (net (code "46") (name "O16") (class "Default")
      (node (ref "LED19") (pin "A") (pinfunction "A_A") (pintype "passive"))
      (node (ref "LED2") (pin "A") (pinfunction "A_A") (pintype "passive"))
      (node (ref "U2") (pin "2") (pinfunction "F_2") (pintype "passive"))
      (node (ref "U4") (pin "28") (pinfunction "O16_28") (pintype "output"))
    )
    (net (code "47") (name "O17") (class "Default")
      (node (ref "LED1") (pin "A") (pinfunction "A_A") (pintype "passive"))
      (node (ref "LED18") (pin "A") (pinfunction "A_A") (pintype "passive"))
      (node (ref "U2") (pin "1") (pinfunction "G_1") (pintype "passive"))
      (node (ref "U4") (pin "29") (pinfunction "O17_29") (pintype "output"))
    )
    (net (code "48") (name "O18") (class "Default")
      (node (ref "LED17") (pin "A") (pinfunction "A_A") (pintype "passive"))
      (node (ref "LED8") (pin "A") (pinfunction "A_A") (pintype "passive"))
      (node (ref "U2") (pin "6") (pinfunction "DP_6") (pintype "passive"))
      (node (ref "U4") (pin "30") (pinfunction "O18_30") (pintype "output"))
    )
    (net (code "49") (name "P0") (class "Default")
      (node (ref "U$2") (pin "A") (pinfunction "A_A") (pintype "passive"))
      (node (ref "U$6") (pin "A") (pinfunction "A_A") (pintype "passive"))
      (node (ref "U4") (pin "36") (pinfunction "P0_36") (pintype "bidirectional"))
    )
    (net (code "50") (name "P1") (class "Default")
      (node (ref "U$3") (pin "A") (pinfunction "A_A") (pintype "passive"))
      (node (ref "U$7") (pin "A") (pinfunction "A_A") (pintype "passive"))
      (node (ref "U4") (pin "37") (pinfunction "P1_37") (pintype "bidirectional"))
    )
    (net (code "51") (name "P2") (class "Default")
      (node (ref "U$4") (pin "A") (pinfunction "A_A") (pintype "passive"))
      (node (ref "U$9") (pin "A") (pinfunction "A_A") (pintype "passive"))
      (node (ref "U4") (pin "33") (pinfunction "P2_33") (pintype "bidirectional"))
    )
    (net (code "52") (name "P3") (class "Default")
      (node (ref "U$5") (pin "A") (pinfunction "A_A") (pintype "passive"))
      (node (ref "U$8") (pin "A") (pinfunction "A_A") (pintype "passive"))
      (node (ref "U4") (pin "34") (pinfunction "P3_34") (pintype "bidirectional"))
    )
    (net (code "53") (name "P4") (class "Default")
      (node (ref "IC3") (pin "32") (pinfunction "PD2(INT0)_32") (pintype "bidirectional"))
      (node (ref "U4") (pin "35") (pinfunction "P4/~{IRQ}_35") (pintype "bidirectional"))
    )
    (net (code "54") (name "R1IN") (class "Default")
      (node (ref "J1") (pin "16") (pinfunction "16_16") (pintype "passive"))
      (node (ref "J1") (pin "18") (pinfunction "18_18") (pintype "passive"))
      (node (ref "U6") (pin "13") (pinfunction "R1IN_13") (pintype "input"))
    )
    (net (code "55") (name "R1OUT") (class "Default")
      (node (ref "IC3") (pin "30") (pinfunction "PD0(RXD)_30") (pintype "bidirectional"))
      (node (ref "U6") (pin "12") (pinfunction "R1OUT_12") (pintype "output"))
    )
    (net (code "56") (name "REG_FB") (class "Default")
      (node (ref "C11") (pin "1") (pinfunction "1_1") (pintype "passive"))
      (node (ref "C13") (pin "1") (pinfunction "1_1") (pintype "passive"))
      (node (ref "C14") (pin "2") (pinfunction "2_2") (pintype "passive"))
      (node (ref "U7") (pin "4") (pinfunction "FEEDBACK_4") (pintype "passive"))
    )
    (net (code "57") (name "REG_P_O") (class "Default")
      (node (ref "C14") (pin "1") (pinfunction "1_1") (pintype "passive"))
      (node (ref "D1") (pin "C") (pinfunction "C_C") (pintype "passive"))
      (node (ref "U7") (pin "2") (pinfunction "OUTPUT_2") (pintype "output"))
    )
    (net (code "58") (name "RELAY_NC") (class "Default")
      (node (ref "J1") (pin "6") (pinfunction "6_6") (pintype "passive"))
      (node (ref "K1") (pin "10") (pinfunction "7_10") (pintype "passive"))
    )
    (net (code "59") (name "RELAY_NO") (class "Default")
      (node (ref "J1") (pin "7") (pinfunction "7_7") (pintype "passive"))
      (node (ref "K1") (pin "8") (pinfunction "5_8") (pintype "passive"))
    )
    (net (code "60") (name "RESET") (class "Default")
      (node (ref "AVRISP") (pin "5") (pinfunction "5_5") (pintype "passive"))
      (node (ref "IC3") (pin "29") (pinfunction "PC6(/RESET)_29") (pintype "bidirectional"))
      (node (ref "R16") (pin "2") (pinfunction "2_2") (pintype "passive"))
      (node (ref "S10") (pin "2") (pinfunction "S1_2") (pintype "passive"))
    )
    (net (code "61") (name "RLY_OUT") (class "Default")
      (node (ref "R14") (pin "1") (pinfunction "1_1") (pintype "passive"))
      (node (ref "R19") (pin "1") (pinfunction "1_1") (pintype "passive"))
    )
    (net (code "62") (name "RX") (class "Default")
      (node (ref "DEBUG") (pin "1") (pinfunction "P$1_1") (pintype "bidirectional"))
      (node (ref "R17") (pin "1") (pinfunction "1_1") (pintype "passive"))
    )
    (net (code "63") (name "SCK") (class "Default")
      (node (ref "AVRISP") (pin "3") (pinfunction "3_3") (pintype "passive"))
      (node (ref "IC3") (pin "17") (pinfunction "PB5(SCK)_17") (pintype "bidirectional"))
      (node (ref "R17") (pin "2") (pinfunction "2_2") (pintype "passive"))
    )
    (net (code "64") (name "SCL") (class "Default")
      (node (ref "IC3") (pin "28") (pinfunction "PC5(ADC5/SCL)_28") (pintype "bidirectional"))
      (node (ref "R7") (pin "2") (pinfunction "2_2") (pintype "passive"))
      (node (ref "U4") (pin "40") (pinfunction "SCL_40") (pintype "input"))
    )
    (net (code "65") (name "SDA") (class "Default")
      (node (ref "IC3") (pin "27") (pinfunction "PC4(ADC4/SDA)_27") (pintype "bidirectional"))
      (node (ref "R6") (pin "2") (pinfunction "2_2") (pintype "passive"))
      (node (ref "U4") (pin "39") (pinfunction "SDA_39") (pintype "bidirectional"))
    )
    (net (code "66") (name "SW_ON") (class "Default")
      (node (ref "IC3") (pin "1") (pinfunction "PD3(INT1)_1") (pintype "bidirectional"))
      (node (ref "R11") (pin "2") (pinfunction "2_2") (pintype "passive"))
      (node (ref "S1") (pin "3") (pinfunction "COM_1_3") (pintype "bidirectional"))
    )
    (net (code "67") (name "T1IN") (class "Default")
      (node (ref "IC3") (pin "31") (pinfunction "PD1(TXD)_31") (pintype "bidirectional"))
      (node (ref "U6") (pin "11") (pinfunction "T1IN_11") (pintype "input"))
    )
    (net (code "68") (name "T1OUT") (class "Default")
      (node (ref "J1") (pin "13") (pinfunction "13_13") (pintype "passive"))
      (node (ref "J1") (pin "17") (pinfunction "17_17") (pintype "passive"))
      (node (ref "U6") (pin "14") (pinfunction "T1OUT_14") (pintype "output"))
    )
    (net (code "69") (name "TX") (class "Default")
      (node (ref "DEBUG") (pin "2") (pinfunction "P$2_2") (pintype "bidirectional"))
      (node (ref "R18") (pin "1") (pinfunction "1_1") (pintype "passive"))
    )
    (net (code "70") (name "VCC") (class "Default")
      (node (ref "AVRISP") (pin "2") (pinfunction "2_2") (pintype "passive"))
      (node (ref "C12") (pin "1") (pinfunction "1_1") (pintype "passive"))
      (node (ref "C13") (pin "2") (pinfunction "2_2") (pintype "passive"))
      (node (ref "C20") (pin "+") (pinfunction "+_+") (pintype "passive"))
      (node (ref "C31") (pin "+") (pinfunction "+_+") (pintype "passive"))
      (node (ref "C33") (pin "2") (pinfunction "2_2") (pintype "passive"))
      (node (ref "C5") (pin "1") (pinfunction "1_1") (pintype "passive"))
      (node (ref "C6") (pin "1") (pinfunction "1_1") (pintype "passive"))
      (node (ref "C7") (pin "2") (pinfunction "2_2") (pintype "passive"))
      (node (ref "DEBUG") (pin "3") (pinfunction "P$3_3") (pintype "bidirectional"))
      (node (ref "IC3") (pin "18") (pinfunction "AVCC_18") (pintype "power_in"))
      (node (ref "IC3") (pin "4") (pinfunction "VCC_4") (pintype "power_in"))
      (node (ref "IC3") (pin "6") (pinfunction "VCC_6") (pintype "power_in"))
      (node (ref "J1") (pin "25") (pinfunction "25_25") (pintype "passive"))
      (node (ref "K1") (pin "1") (pinfunction "1_1") (pintype "passive"))
      (node (ref "MT1") (pin "F1") (pinfunction "VCC_F1") (pintype "bidirectional"))
      (node (ref "R11") (pin "1") (pinfunction "1_1") (pintype "passive"))
      (node (ref "R16") (pin "1") (pinfunction "1_1") (pintype "passive"))
      (node (ref "R5") (pin "2") (pinfunction "2_2") (pintype "passive"))
      (node (ref "R6") (pin "1") (pinfunction "1_1") (pintype "passive"))
      (node (ref "R7") (pin "1") (pinfunction "1_1") (pintype "passive"))
      (node (ref "U4") (pin "16") (pinfunction "V+_2_16") (pintype "power_in"))
      (node (ref "U4") (pin "18") (pinfunction "V+_3_18") (pintype "power_in"))
      (node (ref "U4") (pin "19") (pinfunction "V+_19") (pintype "power_in"))
      (node (ref "U6") (pin "16") (pinfunction "VCC_16") (pintype "bidirectional"))
    )
    (net (code "71") (name "VIN_BRD") (class "Default")
      (node (ref "C10") (pin "+") (pinfunction "+_+") (pintype "passive"))
      (node (ref "J1") (pin "5") (pinfunction "5_5") (pintype "passive"))
      (node (ref "U7") (pin "1") (pinfunction "VIN_1") (pintype "input"))
    )
    (net (code "72") (name "V_BAT") (class "Default")
      (node (ref "IC3") (pin "19") (pinfunction "ADC6_19") (pintype "bidirectional"))
      (node (ref "R12") (pin "1") (pinfunction "1_1") (pintype "passive"))
      (node (ref "R5") (pin "1") (pinfunction "1_1") (pintype "passive"))
    )
    (net (code "73") (name "unconnected-(IC3-PB0(ICP)-Pad12)") (class "Default")
      (node (ref "IC3") (pin "12") (pinfunction "PB0(ICP)_12") (pintype "bidirectional"))
    )
    (net (code "74") (name "unconnected-(IC3-PB1(OC1A)-Pad13)") (class "Default")
      (node (ref "IC3") (pin "13") (pinfunction "PB1(OC1A)_13") (pintype "bidirectional"))
    )
    (net (code "75") (name "unconnected-(IC3-PB2(SS{slash}OC1B)-Pad14)") (class "Default")
      (node (ref "IC3") (pin "14") (pinfunction "PB2(SS/OC1B)_14") (pintype "bidirectional"))
    )
    (net (code "76") (name "unconnected-(IC3-PD4(XCK{slash}T0)-Pad2)") (class "Default")
      (node (ref "IC3") (pin "2") (pinfunction "PD4(XCK/T0)_2") (pintype "bidirectional"))
    )
    (net (code "77") (name "unconnected-(IC3-PD5(T1)-Pad9)") (class "Default")
      (node (ref "IC3") (pin "9") (pinfunction "PD5(T1)_9") (pintype "bidirectional"))
    )
    (net (code "78") (name "unconnected-(IC3-PD6(AIN0)-Pad10)") (class "Default")
      (node (ref "IC3") (pin "10") (pinfunction "PD6(AIN0)_10") (pintype "bidirectional"))
    )
    (net (code "79") (name "unconnected-(IC3-PD7(AIN1)-Pad11)") (class "Default")
      (node (ref "IC3") (pin "11") (pinfunction "PD7(AIN1)_11") (pintype "bidirectional"))
    )
    (net (code "80") (name "unconnected-(J1-Pad2)") (class "Default")
      (node (ref "J1") (pin "2") (pinfunction "2_2") (pintype "passive"))
    )
    (net (code "81") (name "unconnected-(J1-Pad8)") (class "Default")
      (node (ref "J1") (pin "8") (pinfunction "8_8") (pintype "passive"))
    )
    (net (code "82") (name "unconnected-(J1-Pad9)") (class "Default")
      (node (ref "J1") (pin "9") (pinfunction "9_9") (pintype "passive"))
    )
    (net (code "83") (name "unconnected-(J1-Pad10)") (class "Default")
      (node (ref "J1") (pin "10") (pinfunction "10_10") (pintype "passive"))
    )
    (net (code "84") (name "unconnected-(J1-Pad11)") (class "Default")
      (node (ref "J1") (pin "11") (pinfunction "11_11") (pintype "passive"))
    )
    (net (code "85") (name "unconnected-(J1-Pad12)") (class "Default")
      (node (ref "J1") (pin "12") (pinfunction "12_12") (pintype "passive"))
    )
    (net (code "86") (name "unconnected-(J1-Pad14)") (class "Default")
      (node (ref "J1") (pin "14") (pinfunction "14_14") (pintype "passive"))
    )
    (net (code "87") (name "unconnected-(J1-Pad15)") (class "Default")
      (node (ref "J1") (pin "15") (pinfunction "15_15") (pintype "passive"))
    )
    (net (code "88") (name "unconnected-(J1-Pad19)") (class "Default")
      (node (ref "J1") (pin "19") (pinfunction "19_19") (pintype "passive"))
    )
    (net (code "89") (name "unconnected-(J1-Pad20)") (class "Default")
      (node (ref "J1") (pin "20") (pinfunction "20_20") (pintype "passive"))
    )
    (net (code "90") (name "unconnected-(J1-Pad21)") (class "Default")
      (node (ref "J1") (pin "21") (pinfunction "21_21") (pintype "passive"))
    )
    (net (code "91") (name "unconnected-(J1-Pad22)") (class "Default")
      (node (ref "J1") (pin "22") (pinfunction "22_22") (pintype "passive"))
    )
    (net (code "92") (name "unconnected-(J1-Pad23)") (class "Default")
      (node (ref "J1") (pin "23") (pinfunction "23_23") (pintype "passive"))
    )
    (net (code "93") (name "unconnected-(J1-Pad24)") (class "Default")
      (node (ref "J1") (pin "24") (pinfunction "24_24") (pintype "passive"))
    )
    (net (code "94") (name "unconnected-(J1-Pad26)") (class "Default")
      (node (ref "J1") (pin "26") (pinfunction "26_26") (pintype "passive"))
    )
    (net (code "95") (name "unconnected-(K1-2-Pad3)") (class "Default")
      (node (ref "K1") (pin "3") (pinfunction "2_3") (pintype "passive"))
    )
    (net (code "96") (name "unconnected-(K1-3-Pad4)") (class "Default")
      (node (ref "K1") (pin "4") (pinfunction "3_4") (pintype "passive"))
    )
    (net (code "97") (name "unconnected-(K1-4-Pad5)") (class "Default")
      (node (ref "K1") (pin "5") (pinfunction "4_5") (pintype "passive"))
    )
    (net (code "98") (name "unconnected-(LED6-PadC)") (class "Default")
      (node (ref "LED6") (pin "C") (pinfunction "C_C") (pintype "passive"))
    )
    (net (code "99") (name "unconnected-(MT1-SWITCH_OUT-PadF8)") (class "Default")
      (node (ref "MT1") (pin "F8") (pinfunction "SWITCH_OUT_F8") (pintype "bidirectional"))
    )
    (net (code "100") (name "unconnected-(S1-COM_2-Pad4)") (class "Default")
      (node (ref "S1") (pin "4") (pinfunction "COM_2_4") (pintype "bidirectional"))
    )
    (net (code "101") (name "unconnected-(S1-NO_2-Pad2)") (class "Default")
      (node (ref "S1") (pin "2") (pinfunction "NO_2_2") (pintype "bidirectional"))
    )
    (net (code "102") (name "unconnected-(S2-COM_2-Pad4)") (class "Default")
      (node (ref "S2") (pin "4") (pinfunction "COM_2_4") (pintype "bidirectional"))
    )
    (net (code "103") (name "unconnected-(S2-NO_2-Pad2)") (class "Default")
      (node (ref "S2") (pin "2") (pinfunction "NO_2_2") (pintype "bidirectional"))
    )
    (net (code "104") (name "unconnected-(S3-COM_2-Pad4)") (class "Default")
      (node (ref "S3") (pin "4") (pinfunction "COM_2_4") (pintype "bidirectional"))
    )
    (net (code "105") (name "unconnected-(S3-NO_2-Pad2)") (class "Default")
      (node (ref "S3") (pin "2") (pinfunction "NO_2_2") (pintype "bidirectional"))
    )
    (net (code "106") (name "unconnected-(S4-COM_2-Pad4)") (class "Default")
      (node (ref "S4") (pin "4") (pinfunction "COM_2_4") (pintype "bidirectional"))
    )
    (net (code "107") (name "unconnected-(S4-NO_2-Pad2)") (class "Default")
      (node (ref "S4") (pin "2") (pinfunction "NO_2_2") (pintype "bidirectional"))
    )
    (net (code "108") (name "unconnected-(S5-COM_2-Pad4)") (class "Default")
      (node (ref "S5") (pin "4") (pinfunction "COM_2_4") (pintype "bidirectional"))
    )
    (net (code "109") (name "unconnected-(S5-NO_2-Pad2)") (class "Default")
      (node (ref "S5") (pin "2") (pinfunction "NO_2_2") (pintype "bidirectional"))
    )
    (net (code "110") (name "unconnected-(S6-COM_2-Pad4)") (class "Default")
      (node (ref "S6") (pin "4") (pinfunction "COM_2_4") (pintype "bidirectional"))
    )
    (net (code "111") (name "unconnected-(S6-NO_2-Pad2)") (class "Default")
      (node (ref "S6") (pin "2") (pinfunction "NO_2_2") (pintype "bidirectional"))
    )
    (net (code "112") (name "unconnected-(S7-COM_2-Pad4)") (class "Default")
      (node (ref "S7") (pin "4") (pinfunction "COM_2_4") (pintype "bidirectional"))
    )
    (net (code "113") (name "unconnected-(S7-NO_2-Pad2)") (class "Default")
      (node (ref "S7") (pin "2") (pinfunction "NO_2_2") (pintype "bidirectional"))
    )
    (net (code "114") (name "unconnected-(S8-COM_2-Pad4)") (class "Default")
      (node (ref "S8") (pin "4") (pinfunction "COM_2_4") (pintype "bidirectional"))
    )
    (net (code "115") (name "unconnected-(S8-NO_2-Pad2)") (class "Default")
      (node (ref "S8") (pin "2") (pinfunction "NO_2_2") (pintype "bidirectional"))
    )
    (net (code "116") (name "unconnected-(S9-COM_2-Pad4)") (class "Default")
      (node (ref "S9") (pin "4") (pinfunction "COM_2_4") (pintype "bidirectional"))
    )
    (net (code "117") (name "unconnected-(S9-NO_2-Pad2)") (class "Default")
      (node (ref "S9") (pin "2") (pinfunction "NO_2_2") (pintype "bidirectional"))
    )
    (net (code "118") (name "unconnected-(S10-P-Pad3)") (class "Default")
      (node (ref "S10") (pin "3") (pinfunction "P_3") (pintype "passive"))
    )
    (net (code "119") (name "unconnected-(S10-S-Pad1)") (class "Default")
      (node (ref "S10") (pin "1") (pinfunction "S_1") (pintype "passive"))
    )
    (net (code "120") (name "unconnected-(U4-BLINK-Pad31)") (class "Default")
      (node (ref "U4") (pin "31") (pinfunction "BLINK_31") (pintype "output"))
    )
    (net (code "121") (name "unconnected-(U4-NC-Pad20)") (class "Default")
      (node (ref "U4") (pin "20") (pinfunction "NC_20") (pintype "no_connect"))
    )
    (net (code "122") (name "unconnected-(U4-NC_2-Pad11)") (class "Default")
      (node (ref "U4") (pin "11") (pinfunction "NC_2_11") (pintype "no_connect"))
    )
    (net (code "123") (name "unconnected-(U4-OSC_OUT-Pad32)") (class "Default")
      (node (ref "U4") (pin "32") (pinfunction "OSC_OUT_32") (pintype "output"))
    )
    (net (code "124") (name "unconnected-(U6-R2IN-Pad8)") (class "Default")
      (node (ref "U6") (pin "8") (pinfunction "R2IN_8") (pintype "input"))
    )
    (net (code "125") (name "unconnected-(U6-R2OUT-Pad9)") (class "Default")
      (node (ref "U6") (pin "9") (pinfunction "R2OUT_9") (pintype "output"))
    )
    (net (code "126") (name "unconnected-(U6-T2IN-Pad10)") (class "Default")
      (node (ref "U6") (pin "10") (pinfunction "T2IN_10") (pintype "input"))
    )
    (net (code "127") (name "unconnected-(U6-T2OUT-Pad7)") (class "Default")
      (node (ref "U6") (pin "7") (pinfunction "T2OUT_7") (pintype "output"))
    )
  )
)
